# lcdmount.net
KiCad netlist of a schematic drawn in EAGLE
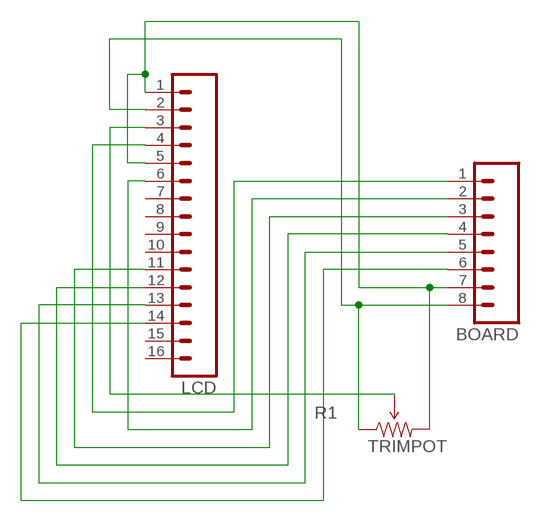
[diagram p0: schematic, sheet 1]

(export (version "E")
  (design (tool "Eeschema 10.0.6"))
  (components
    (comp (ref "BOARD")
      (value "M081X08")
      (footprint "eagle-import:1X08")
      (libsource (lib "eagle-import") (part "M081X08"))
    )
    (comp (ref "LCD")
      (value "M16PTH")
      (footprint "eagle-import:1X16")
      (libsource (lib "eagle-import") (part "M16PTH"))
    )
    (comp (ref "R1")
      (value "TRIMPOT")
      (footprint "eagle-import:3362U-2")
      (libsource (lib "eagle-import") (part "TRIMPOT"))
    )
  )
  (nets
    (net (code "1") (name "Net-(BOARD-Pad1)") (class "Default")
      (node (ref "BOARD") (pin "1") (pinfunction "1_1") (pintype "passive"))
      (node (ref "LCD") (pin "4") (pinfunction "4_4") (pintype "passive"))
    )
    (net (code "2") (name "Net-(BOARD-Pad2)") (class "Default")
      (node (ref "BOARD") (pin "2") (pinfunction "2_2") (pintype "passive"))
      (node (ref "LCD") (pin "6") (pinfunction "6_6") (pintype "passive"))
    )
    (net (code "3") (name "Net-(BOARD-Pad3)") (class "Default")
      (node (ref "BOARD") (pin "3") (pinfunction "3_3") (pintype "passive"))
      (node (ref "LCD") (pin "11") (pinfunction "11_11") (pintype "passive"))
    )
    (net (code "4") (name "Net-(BOARD-Pad4)") (class "Default")
      (node (ref "BOARD") (pin "4") (pinfunction "4_4") (pintype "passive"))
      (node (ref "LCD") (pin "12") (pinfunction "12_12") (pintype "passive"))
    )
    (net (code "5") (name "Net-(BOARD-Pad5)") (class "Default")
      (node (ref "BOARD") (pin "5") (pinfunction "5_5") (pintype "passive"))
      (node (ref "LCD") (pin "13") (pinfunction "13_13") (pintype "passive"))
    )
    (net (code "6") (name "Net-(BOARD-Pad6)") (class "Default")
      (node (ref "BOARD") (pin "6") (pinfunction "6_6") (pintype "passive"))
      (node (ref "LCD") (pin "14") (pinfunction "14_14") (pintype "passive"))
    )
    (net (code "7") (name "Net-(R1-CCW)") (class "Default")
      (node (ref "BOARD") (pin "8") (pinfunction "8_8") (pintype "passive"))
      (node (ref "LCD") (pin "2") (pinfunction "2_2") (pintype "passive"))
      (node (ref "R1") (pin "1") (pinfunction "CCW_1") (pintype "passive"))
    )
    (net (code "8") (name "Net-(R1-CW)") (class "Default")
      (node (ref "BOARD") (pin "7") (pinfunction "7_7") (pintype "passive"))
      (node (ref "LCD") (pin "1") (pinfunction "1_1") (pintype "passive"))
      (node (ref "LCD") (pin "5") (pinfunction "5_5") (pintype "passive"))
      (node (ref "R1") (pin "3") (pinfunction "CW_3") (pintype "passive"))
    )
    (net (code "9") (name "Net-(R1-WIPER)") (class "Default")
      (node (ref "LCD") (pin "3") (pinfunction "3_3") (pintype "passive"))
      (node (ref "R1") (pin "2") (pinfunction "WIPER_2") (pintype "passive"))
    )
    (net (code "10") (name "unconnected-(LCD-Pad7)") (class "Default")
      (node (ref "LCD") (pin "7") (pinfunction "7_7") (pintype "passive"))
    )
    (net (code "11") (name "unconnected-(LCD-Pad8)") (class "Default")
      (node (ref "LCD") (pin "8") (pinfunction "8_8") (pintype "passive"))
    )
    (net (code "12") (name "unconnected-(LCD-Pad9)") (class "Default")
      (node (ref "LCD") (pin "9") (pinfunction "9_9") (pintype "passive"))
    )
    (net (code "13") (name "unconnected-(LCD-Pad10)") (class "Default")
      (node (ref "LCD") (pin "10") (pinfunction "10_10") (pintype "passive"))
    )
    (net (code "14") (name "unconnected-(LCD-Pad15)") (class "Default")
      (node (ref "LCD") (pin "15") (pinfunction "15_15") (pintype "passive"))
    )
    (net (code "15") (name "unconnected-(LCD-Pad16)") (class "Default")
      (node (ref "LCD") (pin "16") (pinfunction "16_16") (pintype "passive"))
    )
  )
)
